# ThermalCamera.net
KiCad netlist of a schematic drawn in EAGLE
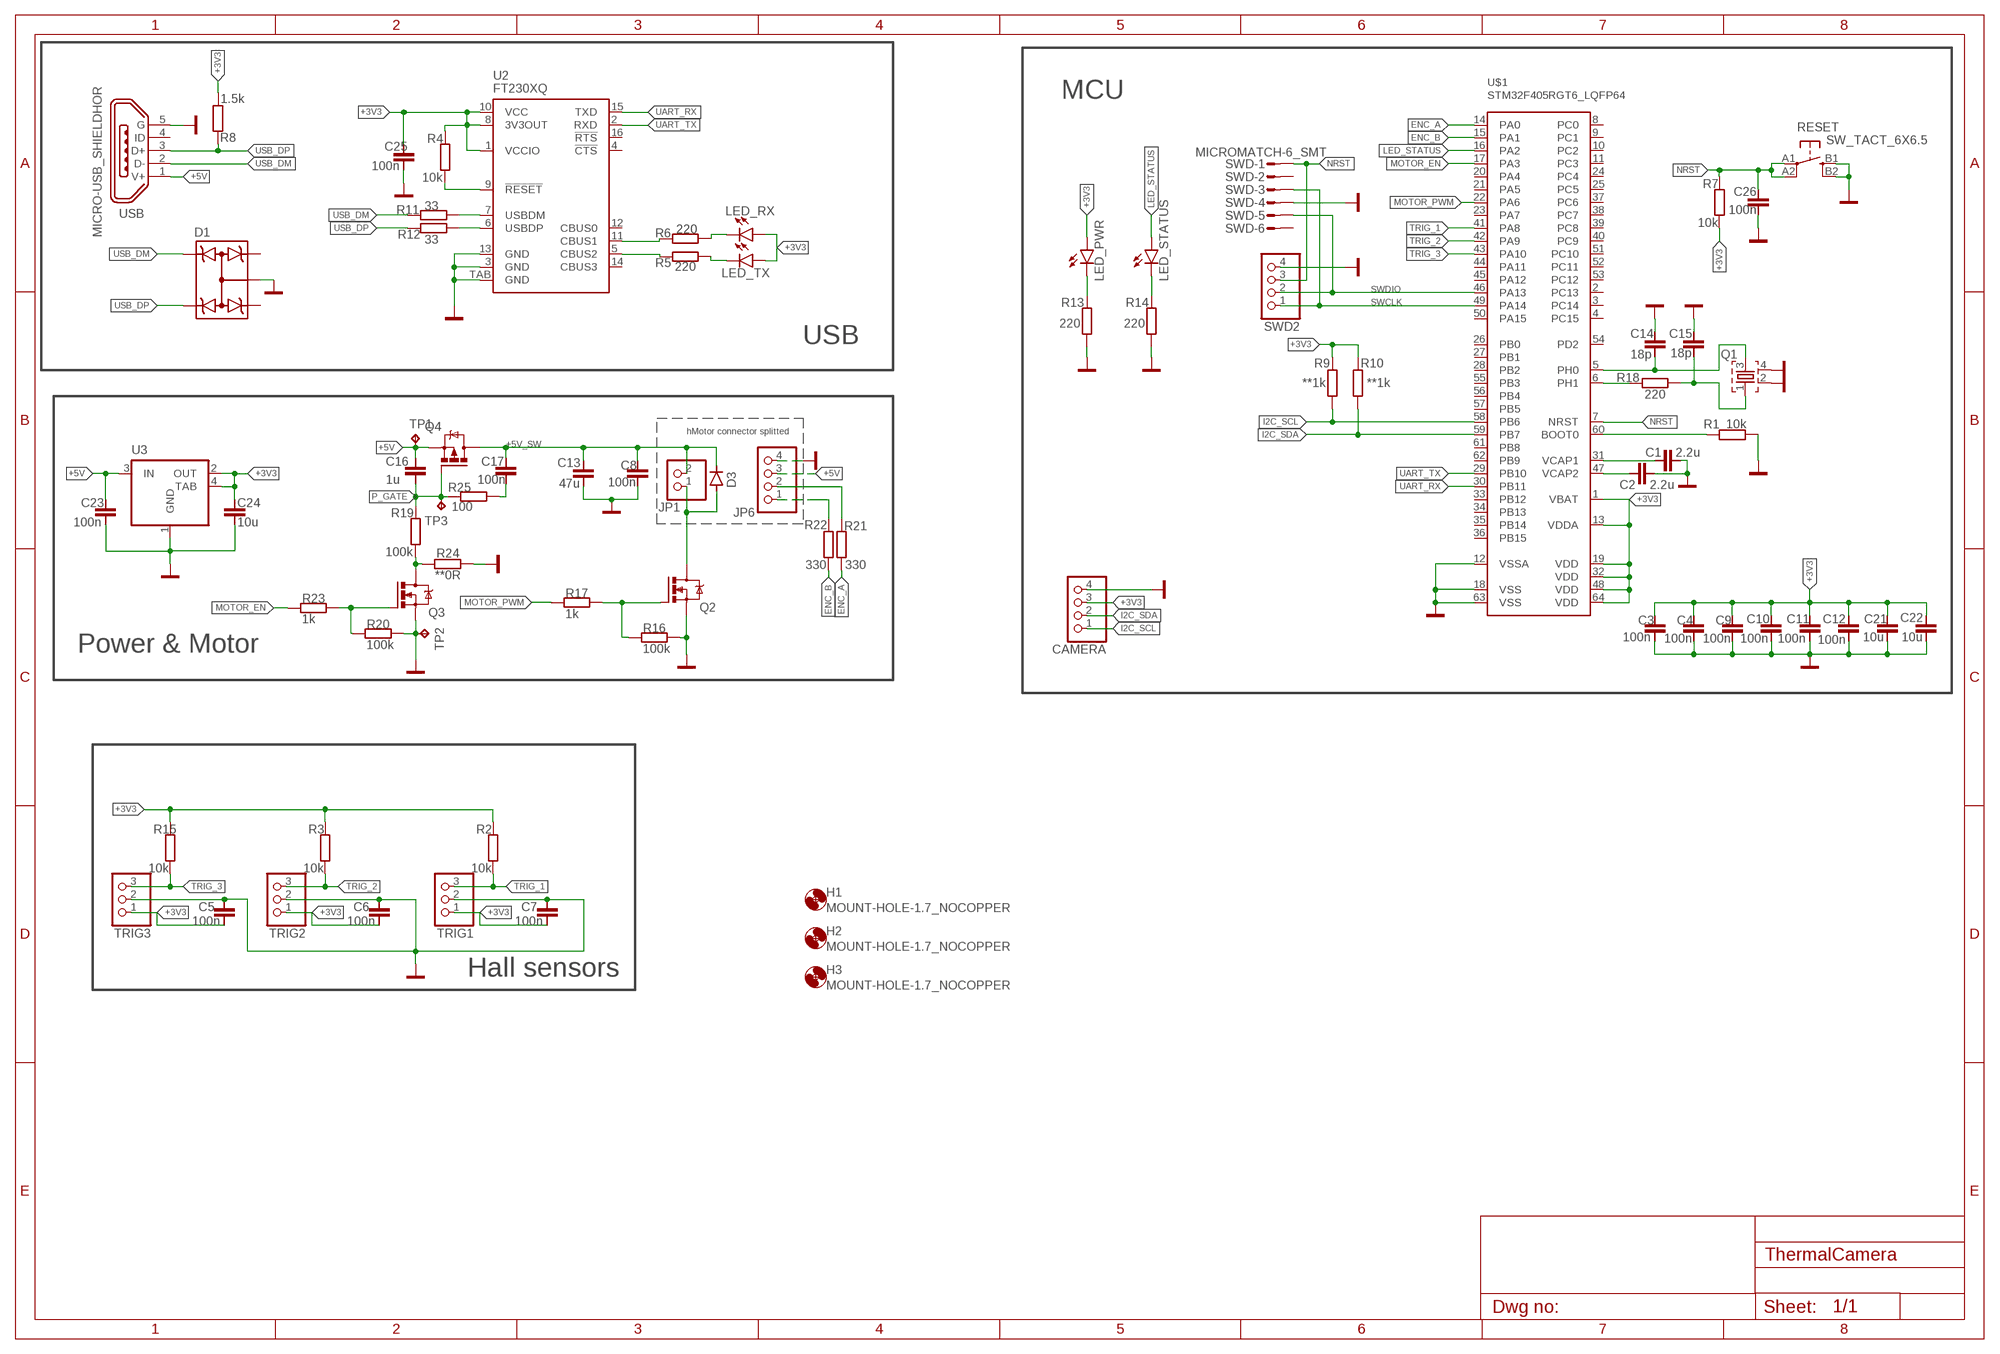
[diagram p0: schematic, sheet 1]

(export (version "E")
  (design (tool "Eeschema 10.0.6"))
  (components
    (comp (ref "C1")
      (value "2.2u")
      (footprint "eagle-import:0603")
      (libsource (lib "eagle-import") (part "CAP_H-0603"))
    )
    (comp (ref "C2")
      (value "2.2u")
      (footprint "eagle-import:0603")
      (libsource (lib "eagle-import") (part "CAP_H-0603"))
    )
    (comp (ref "C3")
      (value "100n")
      (footprint "eagle-import:0603")
      (libsource (lib "eagle-import") (part "CAP_H-0603"))
    )
    (comp (ref "C4")
      (value "100n")
      (footprint "eagle-import:0603")
      (libsource (lib "eagle-import") (part "CAP_H-0603"))
    )
    (comp (ref "C5")
      (value "100n")
      (footprint "eagle-import:0603")
      (libsource (lib "eagle-import") (part "CAP_H-0603"))
    )
    (comp (ref "C6")
      (value "100n")
      (footprint "eagle-import:0603")
      (libsource (lib "eagle-import") (part "CAP_H-0603"))
    )
    (comp (ref "C7")
      (value "100n")
      (footprint "eagle-import:0603")
      (libsource (lib "eagle-import") (part "CAP_H-0603"))
    )
    (comp (ref "C8")
      (value "100n")
      (footprint "eagle-import:0603")
      (libsource (lib "eagle-import") (part "CAP_H-0603"))
    )
    (comp (ref "C9")
      (value "100n")
      (footprint "eagle-import:0603")
      (libsource (lib "eagle-import") (part "CAP_H-0603"))
    )
    (comp (ref "C10")
      (value "100n")
      (footprint "eagle-import:0603")
      (libsource (lib "eagle-import") (part "CAP_H-0603"))
    )
    (comp (ref "C11")
      (value "100n")
      (footprint "eagle-import:0603")
      (libsource (lib "eagle-import") (part "CAP_H-0603"))
    )
    (comp (ref "C12")
      (value "100n")
      (footprint "eagle-import:0603")
      (libsource (lib "eagle-import") (part "CAP_H-0603"))
    )
    (comp (ref "C13")
      (value "47u")
      (footprint "eagle-import:0805")
      (libsource (lib "eagle-import") (part "CAP_H-0805"))
    )
    (comp (ref "C14")
      (value "18p")
      (footprint "eagle-import:0603")
      (libsource (lib "eagle-import") (part "CAP_H-0603"))
    )
    (comp (ref "C15")
      (value "18p")
      (footprint "eagle-import:0603")
      (libsource (lib "eagle-import") (part "CAP_H-0603"))
    )
    (comp (ref "C16")
      (value "1u")
      (footprint "eagle-import:0603")
      (libsource (lib "eagle-import") (part "CAP_H-0603"))
    )
    (comp (ref "C17")
      (value "100n")
      (footprint "eagle-import:0603")
      (libsource (lib "eagle-import") (part "CAP_H-0603"))
    )
    (comp (ref "C21")
      (value "10u")
      (footprint "eagle-import:0603")
      (libsource (lib "eagle-import") (part "CAP_H-0603"))
    )
    (comp (ref "C22")
      (value "10u")
      (footprint "eagle-import:0603")
      (libsource (lib "eagle-import") (part "CAP_H-0603"))
    )
    (comp (ref "C23")
      (value "100n")
      (footprint "eagle-import:0603")
      (libsource (lib "eagle-import") (part "CAP_H-0603"))
    )
    (comp (ref "C24")
      (value "10u")
      (footprint "eagle-import:0603")
      (libsource (lib "eagle-import") (part "CAP_H-0603"))
    )
    (comp (ref "C25")
      (value "100n")
      (footprint "eagle-import:0603")
      (libsource (lib "eagle-import") (part "CAP_H-0603"))
    )
    (comp (ref "C26")
      (value "100n")
      (footprint "eagle-import:0603")
      (libsource (lib "eagle-import") (part "CAP_H-0603"))
    )
    (comp (ref "CAMERA")
      (value "PINHD-1X4")
      (footprint "eagle-import:1X04")
      (fields (field (name "SPICEPREFIX") "E"))
      (libsource (lib "eagle-import") (part "PINHD-1X4"))
    )
    (comp (ref "D1")
      (value "TRANSIL-4")
      (footprint "eagle-import:SOT323-5")
      (libsource (lib "eagle-import") (part "TRANSIL-4"))
    )
    (comp (ref "D3")
      (value "BAR63-03")
      (footprint "eagle-import:SOD323")
      (libsource (lib "eagle-import") (part "BAR63-03"))
    )
    (comp (ref "H1")
      (value "MOUNT-HOLE-1.7_NOCOPPER")
      (footprint "eagle-import:1.7-NO_COPPER")
      (libsource (lib "eagle-import") (part "MOUNT-HOLE-1.7_NOCOPPER"))
    )
    (comp (ref "H2")
      (value "MOUNT-HOLE-1.7_NOCOPPER")
      (footprint "eagle-import:1.7-NO_COPPER")
      (libsource (lib "eagle-import") (part "MOUNT-HOLE-1.7_NOCOPPER"))
    )
    (comp (ref "H3")
      (value "MOUNT-HOLE-1.7_NOCOPPER")
      (footprint "eagle-import:1.7-NO_COPPER")
      (libsource (lib "eagle-import") (part "MOUNT-HOLE-1.7_NOCOPPER"))
    )
    (comp (ref "JP1")
      (value "PINHD-1X2")
      (footprint "eagle-import:1X02")
      (libsource (lib "eagle-import") (part "PINHD-1X2"))
    )
    (comp (ref "JP6")
      (value "PINHD-1X4")
      (footprint "eagle-import:1X04")
      (fields (field (name "SPICEPREFIX") "E"))
      (libsource (lib "eagle-import") (part "PINHD-1X4"))
    )
    (comp (ref "LED_PWR")
      (value "LEDCHIPLED_0603")
      (footprint "eagle-import:CHIPLED_0603")
      (libsource (lib "eagle-import") (part "LEDCHIPLED_0603"))
    )
    (comp (ref "LED_RX")
      (value "LEDCHIPLED_0603")
      (footprint "eagle-import:CHIPLED_0603")
      (libsource (lib "eagle-import") (part "LEDCHIPLED_0603"))
    )
    (comp (ref "LED_STATUS")
      (value "LEDCHIPLED_0603")
      (footprint "eagle-import:CHIPLED_0603")
      (libsource (lib "eagle-import") (part "LEDCHIPLED_0603"))
    )
    (comp (ref "LED_TX")
      (value "LEDCHIPLED_0603")
      (footprint "eagle-import:CHIPLED_0603")
      (libsource (lib "eagle-import") (part "LEDCHIPLED_0603"))
    )
    (comp (ref "Q1")
      (value "CRYSTAL_4PIN-5X3.2")
      (footprint "eagle-import:CRYSTAL_5X3.2_4PIN")
      (libsource (lib "eagle-import") (part "CRYSTAL_4PIN-5X3.2"))
    )
    (comp (ref "Q2")
      (value "NMOS-SOT23")
      (footprint "eagle-import:SOT23")
      (libsource (lib "eagle-import") (part "NMOS-SOT23"))
    )
    (comp (ref "Q3")
      (value "NMOS-SOT23")
      (footprint "eagle-import:SOT23")
      (libsource (lib "eagle-import") (part "NMOS-SOT23"))
    )
    (comp (ref "Q4")
      (value "PMOS-SOT23")
      (footprint "eagle-import:SOT23")
      (libsource (lib "eagle-import") (part "PMOS-SOT23"))
    )
    (comp (ref "R1")
      (value "10k")
      (footprint "eagle-import:0603")
      (libsource (lib "eagle-import") (part "RES_H-0603"))
    )
    (comp (ref "R2")
      (value "10k")
      (footprint "eagle-import:0603")
      (libsource (lib "eagle-import") (part "RES_H-0603"))
    )
    (comp (ref "R3")
      (value "10k")
      (footprint "eagle-import:0603")
      (libsource (lib "eagle-import") (part "RES_H-0603"))
    )
    (comp (ref "R4")
      (value "10k")
      (footprint "eagle-import:0603")
      (libsource (lib "eagle-import") (part "RES_H-0603"))
    )
    (comp (ref "R5")
      (value "220")
      (footprint "eagle-import:0603")
      (libsource (lib "eagle-import") (part "RES_H-0603"))
    )
    (comp (ref "R6")
      (value "220")
      (footprint "eagle-import:0603")
      (libsource (lib "eagle-import") (part "RES_H-0603"))
    )
    (comp (ref "R7")
      (value "10k")
      (footprint "eagle-import:0603")
      (libsource (lib "eagle-import") (part "RES_H-0603"))
    )
    (comp (ref "R8")
      (value "1.5k")
      (footprint "eagle-import:0603")
      (libsource (lib "eagle-import") (part "RES_H-0603"))
    )
    (comp (ref "R9")
      (value "**1k")
      (footprint "eagle-import:0603")
      (libsource (lib "eagle-import") (part "RES_H-0603"))
    )
    (comp (ref "R10")
      (value "**1k")
      (footprint "eagle-import:0603")
      (libsource (lib "eagle-import") (part "RES_H-0603"))
    )
    (comp (ref "R11")
      (value "33")
      (footprint "eagle-import:0603")
      (libsource (lib "eagle-import") (part "RES_H-0603"))
    )
    (comp (ref "R12")
      (value "33")
      (footprint "eagle-import:0603")
      (libsource (lib "eagle-import") (part "RES_H-0603"))
    )
    (comp (ref "R13")
      (value "220")
      (footprint "eagle-import:0603")
      (libsource (lib "eagle-import") (part "RES_H-0603"))
    )
    (comp (ref "R14")
      (value "220")
      (footprint "eagle-import:0603")
      (libsource (lib "eagle-import") (part "RES_H-0603"))
    )
    (comp (ref "R15")
      (value "10k")
      (footprint "eagle-import:0603")
      (libsource (lib "eagle-import") (part "RES_H-0603"))
    )
    (comp (ref "R16")
      (value "100k")
      (footprint "eagle-import:0603")
      (libsource (lib "eagle-import") (part "RES_H-0603"))
    )
    (comp (ref "R17")
      (value "1k")
      (footprint "eagle-import:0603")
      (libsource (lib "eagle-import") (part "RES_H-0603"))
    )
    (comp (ref "R18")
      (value "220")
      (footprint "eagle-import:0603")
      (libsource (lib "eagle-import") (part "RES_H-0603"))
    )
    (comp (ref "R19")
      (value "100k")
      (footprint "eagle-import:0603")
      (libsource (lib "eagle-import") (part "RES_H-0603"))
    )
    (comp (ref "R20")
      (value "100k")
      (footprint "eagle-import:0603")
      (libsource (lib "eagle-import") (part "RES_H-0603"))
    )
    (comp (ref "R21")
      (value "330")
      (footprint "eagle-import:0603")
      (libsource (lib "eagle-import") (part "RES_H-0603"))
    )
    (comp (ref "R22")
      (value "330")
      (footprint "eagle-import:0603")
      (libsource (lib "eagle-import") (part "RES_H-0603"))
    )
    (comp (ref "R23")
      (value "1k")
      (footprint "eagle-import:0603")
      (libsource (lib "eagle-import") (part "RES_H-0603"))
    )
    (comp (ref "R24")
      (value "**0R")
      (footprint "eagle-import:0603")
      (libsource (lib "eagle-import") (part "RES_H-0603"))
    )
    (comp (ref "R25")
      (value "100")
      (footprint "eagle-import:0603")
      (libsource (lib "eagle-import") (part "RES_H-0603"))
    )
    (comp (ref "RESET")
      (value "SW_TACT_6X6.5")
      (footprint "eagle-import:SW_TACT_6X6.5")
      (libsource (lib "eagle-import") (part "SW_TACT_6X6.5"))
    )
    (comp (ref "SWD")
      (value "MICROMATCH-6_SMT")
      (footprint "eagle-import:MICROMATCH-6_SMT")
      (libsource (lib "eagle-import") (part "MICROMATCH-6_SMT"))
    )
    (comp (ref "SWD2")
      (value "PINHD-1X4")
      (footprint "eagle-import:1X04")
      (libsource (lib "eagle-import") (part "PINHD-1X4"))
    )
    (comp (ref "TP1")
      (value "TPTP12R")
      (footprint "eagle-import:TP12R")
      (libsource (lib "eagle-import") (part "TPTP12R"))
    )
    (comp (ref "TP2")
      (value "TPTP12R")
      (footprint "eagle-import:TP12R")
      (libsource (lib "eagle-import") (part "TPTP12R"))
    )
    (comp (ref "TP3")
      (value "TPTP06R")
      (footprint "eagle-import:TP06R")
      (libsource (lib "eagle-import") (part "TPTP06R"))
    )
    (comp (ref "TRIG1")
      (value "PINHD-1X3")
      (footprint "eagle-import:1X03")
      (libsource (lib "eagle-import") (part "PINHD-1X3"))
    )
    (comp (ref "TRIG2")
      (value "PINHD-1X3")
      (footprint "eagle-import:1X03")
      (libsource (lib "eagle-import") (part "PINHD-1X3"))
    )
    (comp (ref "TRIG3")
      (value "PINHD-1X3")
      (footprint "eagle-import:1X03")
      (libsource (lib "eagle-import") (part "PINHD-1X3"))
    )
    (comp (ref "U$1")
      (value "STM32F405RGT6_LQFP64")
      (footprint "eagle-import:SQFP-S-10X10-64")
      (libsource (lib "eagle-import") (part "STM32F40XXX_LQFP64"))
    )
    (comp (ref "U2")
      (value "FT230XQ")
      (footprint "eagle-import:QFN16")
      (libsource (lib "eagle-import") (part "FT230XQ"))
    )
    (comp (ref "U3")
      (value "REG1117")
      (footprint "eagle-import:SOT223")
      (libsource (lib "eagle-import") (part "REG1117"))
    )
    (comp (ref "USB")
      (value "MICRO-USB_SHIELDHOR")
      (footprint "eagle-import:MICRO_USB_6_SHIELD")
      (libsource (lib "eagle-import") (part "MICRO-USB_SHIELDHOR"))
    )
  )
  (nets
    (net (code "1") (name "+3V3") (class "Default")
      (node (ref "C10") (pin "1") (pinfunction "1_1") (pintype "passive"))
      (node (ref "C11") (pin "1") (pinfunction "1_1") (pintype "passive"))
      (node (ref "C12") (pin "1") (pinfunction "1_1") (pintype "passive"))
      (node (ref "C21") (pin "1") (pinfunction "1_1") (pintype "passive"))
      (node (ref "C22") (pin "1") (pinfunction "1_1") (pintype "passive"))
      (node (ref "C24") (pin "1") (pinfunction "1_1") (pintype "passive"))
      (node (ref "C25") (pin "1") (pinfunction "1_1") (pintype "passive"))
      (node (ref "C3") (pin "1") (pinfunction "1_1") (pintype "passive"))
      (node (ref "C4") (pin "1") (pinfunction "1_1") (pintype "passive"))
      (node (ref "C5") (pin "2") (pinfunction "2_2") (pintype "passive"))
      (node (ref "C6") (pin "2") (pinfunction "2_2") (pintype "passive"))
      (node (ref "C7") (pin "2") (pinfunction "2_2") (pintype "passive"))
      (node (ref "C9") (pin "1") (pinfunction "1_1") (pintype "passive"))
      (node (ref "CAMERA") (pin "3") (pinfunction "3_3") (pintype "passive"))
      (node (ref "LED_PWR") (pin "A") (pinfunction "A_A") (pintype "passive"))
      (node (ref "LED_RX") (pin "A") (pinfunction "A_A") (pintype "passive"))
      (node (ref "LED_TX") (pin "A") (pinfunction "A_A") (pintype "passive"))
      (node (ref "R10") (pin "2") (pinfunction "2_2") (pintype "passive"))
      (node (ref "R15") (pin "2") (pinfunction "2_2") (pintype "passive"))
      (node (ref "R2") (pin "2") (pinfunction "2_2") (pintype "passive"))
      (node (ref "R3") (pin "2") (pinfunction "2_2") (pintype "passive"))
      (node (ref "R4") (pin "2") (pinfunction "2_2") (pintype "passive"))
      (node (ref "R7") (pin "1") (pinfunction "1_1") (pintype "passive"))
      (node (ref "R8") (pin "1") (pinfunction "1_1") (pintype "passive"))
      (node (ref "R9") (pin "2") (pinfunction "2_2") (pintype "passive"))
      (node (ref "TRIG1") (pin "1") (pinfunction "1_1") (pintype "passive"))
      (node (ref "TRIG2") (pin "1") (pinfunction "1_1") (pintype "passive"))
      (node (ref "TRIG3") (pin "1") (pinfunction "1_1") (pintype "passive"))
      (node (ref "U$1") (pin "1") (pinfunction "VBAT_1") (pintype "bidirectional"))
      (node (ref "U$1") (pin "13") (pinfunction "VDDA_13") (pintype "bidirectional"))
      (node (ref "U$1") (pin "19") (pinfunction "VDD_19") (pintype "bidirectional"))
      (node (ref "U$1") (pin "32") (pinfunction "VDD_32") (pintype "bidirectional"))
      (node (ref "U$1") (pin "48") (pinfunction "VDD_48") (pintype "bidirectional"))
      (node (ref "U$1") (pin "64") (pinfunction "VDD_64") (pintype "bidirectional"))
      (node (ref "U2") (pin "1") (pinfunction "VCCIO_1") (pintype "power_in"))
      (node (ref "U2") (pin "10") (pinfunction "VCC_10") (pintype "power_in"))
      (node (ref "U2") (pin "8") (pinfunction "3V3OUT_8") (pintype "output"))
      (node (ref "U3") (pin "2") (pinfunction "OUT_2") (pintype "output"))
      (node (ref "U3") (pin "4") (pinfunction "TAB_4") (pintype "output"))
    )
    (net (code "2") (name "+5V") (class "Default")
      (node (ref "C16") (pin "1") (pinfunction "1_1") (pintype "passive"))
      (node (ref "C23") (pin "1") (pinfunction "1_1") (pintype "passive"))
      (node (ref "JP6") (pin "3") (pinfunction "3_3") (pintype "passive"))
      (node (ref "Q4") (pin "2") (pinfunction "S_2") (pintype "passive"))
      (node (ref "TP1") (pin "TP") (pinfunction "TP_TP") (pintype "input"))
      (node (ref "U3") (pin "3") (pinfunction "IN_3") (pintype "input"))
      (node (ref "USB") (pin "1") (pinfunction "V+_1") (pintype "passive"))
    )
    (net (code "3") (name "/+5V_SW") (class "Default")
      (node (ref "C13") (pin "1") (pinfunction "1_1") (pintype "passive"))
      (node (ref "C17") (pin "1") (pinfunction "1_1") (pintype "passive"))
      (node (ref "C8") (pin "1") (pinfunction "1_1") (pintype "passive"))
      (node (ref "D3") (pin "1") (pinfunction "C_1") (pintype "passive"))
      (node (ref "JP1") (pin "2") (pinfunction "2_2") (pintype "passive"))
      (node (ref "Q4") (pin "3") (pinfunction "D_3") (pintype "passive"))
    )
    (net (code "4") (name "/SWCLK") (class "Default")
      (node (ref "SWD") (pin "P$3") (pinfunction "S_P$3") (pintype "passive"))
      (node (ref "SWD2") (pin "1") (pinfunction "1_1") (pintype "passive"))
      (node (ref "U$1") (pin "49") (pinfunction "PA14_49") (pintype "bidirectional"))
    )
    (net (code "5") (name "/SWDIO") (class "Default")
      (node (ref "SWD") (pin "P$5") (pinfunction "S_P$5") (pintype "passive"))
      (node (ref "SWD2") (pin "2") (pinfunction "2_2") (pintype "passive"))
      (node (ref "U$1") (pin "46") (pinfunction "PA13_46") (pintype "bidirectional"))
    )
    (net (code "6") (name "ENC_A") (class "Default")
      (node (ref "R21") (pin "2") (pinfunction "2_2") (pintype "passive"))
      (node (ref "U$1") (pin "14") (pinfunction "PA0_14") (pintype "bidirectional"))
    )
    (net (code "7") (name "ENC_B") (class "Default")
      (node (ref "R22") (pin "1") (pinfunction "1_1") (pintype "passive"))
      (node (ref "U$1") (pin "15") (pinfunction "PA1_15") (pintype "bidirectional"))
    )
    (net (code "8") (name "GND") (class "Default")
      (node (ref "C1") (pin "2") (pinfunction "2_2") (pintype "passive"))
      (node (ref "C10") (pin "2") (pinfunction "2_2") (pintype "passive"))
      (node (ref "C11") (pin "2") (pinfunction "2_2") (pintype "passive"))
      (node (ref "C12") (pin "2") (pinfunction "2_2") (pintype "passive"))
      (node (ref "C13") (pin "2") (pinfunction "2_2") (pintype "passive"))
      (node (ref "C14") (pin "1") (pinfunction "1_1") (pintype "passive"))
      (node (ref "C15") (pin "1") (pinfunction "1_1") (pintype "passive"))
      (node (ref "C2") (pin "2") (pinfunction "2_2") (pintype "passive"))
      (node (ref "C21") (pin "2") (pinfunction "2_2") (pintype "passive"))
      (node (ref "C22") (pin "2") (pinfunction "2_2") (pintype "passive"))
      (node (ref "C23") (pin "2") (pinfunction "2_2") (pintype "passive"))
      (node (ref "C24") (pin "2") (pinfunction "2_2") (pintype "passive"))
      (node (ref "C25") (pin "2") (pinfunction "2_2") (pintype "passive"))
      (node (ref "C26") (pin "2") (pinfunction "2_2") (pintype "passive"))
      (node (ref "C3") (pin "2") (pinfunction "2_2") (pintype "passive"))
      (node (ref "C4") (pin "2") (pinfunction "2_2") (pintype "passive"))
      (node (ref "C5") (pin "1") (pinfunction "1_1") (pintype "passive"))
      (node (ref "C6") (pin "1") (pinfunction "1_1") (pintype "passive"))
      (node (ref "C7") (pin "1") (pinfunction "1_1") (pintype "passive"))
      (node (ref "C8") (pin "2") (pinfunction "2_2") (pintype "passive"))
      (node (ref "C9") (pin "2") (pinfunction "2_2") (pintype "passive"))
      (node (ref "CAMERA") (pin "4") (pinfunction "4_4") (pintype "passive"))
      (node (ref "D1") (pin "2") (pinfunction "2_2") (pintype "passive"))
      (node (ref "JP6") (pin "4") (pinfunction "4_4") (pintype "passive"))
      (node (ref "Q1") (pin "2") (pinfunction "2_2") (pintype "passive"))
      (node (ref "Q1") (pin "4") (pinfunction "4_4") (pintype "passive"))
      (node (ref "Q2") (pin "2") (pinfunction "S_2") (pintype "passive"))
      (node (ref "Q3") (pin "2") (pinfunction "S_2") (pintype "passive"))
      (node (ref "R1") (pin "2") (pinfunction "2_2") (pintype "passive"))
      (node (ref "R13") (pin "2") (pinfunction "2_2") (pintype "passive"))
      (node (ref "R14") (pin "2") (pinfunction "2_2") (pintype "passive"))
      (node (ref "R16") (pin "1") (pinfunction "1_1") (pintype "passive"))
      (node (ref "R20") (pin "1") (pinfunction "1_1") (pintype "passive"))
      (node (ref "R24") (pin "1") (pinfunction "1_1") (pintype "passive"))
      (node (ref "RESET") (pin "B1") (pinfunction "S_B1") (pintype "passive"))
      (node (ref "RESET") (pin "B2") (pinfunction "S1_B2") (pintype "passive"))
      (node (ref "SWD") (pin "P$4") (pinfunction "S_P$4") (pintype "passive"))
      (node (ref "SWD2") (pin "4") (pinfunction "4_4") (pintype "passive"))
      (node (ref "TP2") (pin "TP") (pinfunction "TP_TP") (pintype "input"))
      (node (ref "TRIG1") (pin "2") (pinfunction "2_2") (pintype "passive"))
      (node (ref "TRIG2") (pin "2") (pinfunction "2_2") (pintype "passive"))
      (node (ref "TRIG3") (pin "2") (pinfunction "2_2") (pintype "passive"))
      (node (ref "U$1") (pin "12") (pinfunction "VSSA_12") (pintype "bidirectional"))
      (node (ref "U$1") (pin "18") (pinfunction "VSS_18") (pintype "bidirectional"))
      (node (ref "U$1") (pin "63") (pinfunction "VSS_63") (pintype "bidirectional"))
      (node (ref "U2") (pin "13") (pinfunction "GND_13") (pintype "power_in"))
      (node (ref "U2") (pin "3") (pinfunction "GND_3") (pintype "power_in"))
      (node (ref "U2") (pin "TAB") (pinfunction "GND_TAB") (pintype "power_in"))
      (node (ref "U3") (pin "1") (pinfunction "GND_1") (pintype "power_in"))
      (node (ref "USB") (pin "5") (pinfunction "G_5") (pintype "passive"))
    )
    (net (code "9") (name "I2C_SCL") (class "Default")
      (node (ref "CAMERA") (pin "1") (pinfunction "1_1") (pintype "passive"))
      (node (ref "R9") (pin "1") (pinfunction "1_1") (pintype "passive"))
      (node (ref "U$1") (pin "58") (pinfunction "PB6_58") (pintype "bidirectional"))
    )
    (net (code "10") (name "I2C_SDA") (class "Default")
      (node (ref "CAMERA") (pin "2") (pinfunction "2_2") (pintype "passive"))
      (node (ref "R10") (pin "1") (pinfunction "1_1") (pintype "passive"))
      (node (ref "U$1") (pin "59") (pinfunction "PB7_59") (pintype "bidirectional"))
    )
    (net (code "11") (name "LED_STATUS") (class "Default")
      (node (ref "LED_STATUS") (pin "A") (pinfunction "A_A") (pintype "passive"))
      (node (ref "U$1") (pin "16") (pinfunction "PA2_16") (pintype "bidirectional"))
    )
    (net (code "12") (name "MOTOR_EN") (class "Default")
      (node (ref "R23") (pin "2") (pinfunction "2_2") (pintype "passive"))
      (node (ref "U$1") (pin "17") (pinfunction "PA3_17") (pintype "bidirectional"))
    )
    (net (code "13") (name "MOTOR_PWM") (class "Default")
      (node (ref "R17") (pin "2") (pinfunction "2_2") (pintype "passive"))
      (node (ref "U$1") (pin "22") (pinfunction "PA6_22") (pintype "bidirectional"))
    )
    (net (code "14") (name "NRST") (class "Default")
      (node (ref "C26") (pin "1") (pinfunction "1_1") (pintype "passive"))
      (node (ref "R7") (pin "2") (pinfunction "2_2") (pintype "passive"))
      (node (ref "RESET") (pin "A1") (pinfunction "P_A1") (pintype "passive"))
      (node (ref "RESET") (pin "A2") (pinfunction "P1_A2") (pintype "passive"))
      (node (ref "SWD") (pin "P$1") (pinfunction "S_P$1") (pintype "passive"))
      (node (ref "SWD2") (pin "3") (pinfunction "3_3") (pintype "passive"))
      (node (ref "U$1") (pin "7") (pinfunction "NRST_7") (pintype "bidirectional"))
    )
    (net (code "15") (name "Net-(C15-Pad2)") (class "Default")
      (node (ref "C15") (pin "2") (pinfunction "2_2") (pintype "passive"))
      (node (ref "Q1") (pin "1") (pinfunction "1_1") (pintype "passive"))
      (node (ref "R18") (pin "2") (pinfunction "2_2") (pintype "passive"))
    )
    (net (code "16") (name "Net-(C17-Pad2)") (class "Default")
      (node (ref "C17") (pin "2") (pinfunction "2_2") (pintype "passive"))
      (node (ref "R25") (pin "1") (pinfunction "1_1") (pintype "passive"))
    )
    (net (code "17") (name "Net-(D3-A)") (class "Default")
      (node (ref "D3") (pin "2") (pinfunction "A_2") (pintype "passive"))
      (node (ref "JP1") (pin "1") (pinfunction "1_1") (pintype "passive"))
      (node (ref "Q2") (pin "3") (pinfunction "D_3") (pintype "passive"))
    )
    (net (code "18") (name "Net-(JP6-Pad1)") (class "Default")
      (node (ref "JP6") (pin "1") (pinfunction "1_1") (pintype "passive"))
      (node (ref "R22") (pin "2") (pinfunction "2_2") (pintype "passive"))
    )
    (net (code "19") (name "Net-(JP6-Pad2)") (class "Default")
      (node (ref "JP6") (pin "2") (pinfunction "2_2") (pintype "passive"))
      (node (ref "R21") (pin "1") (pinfunction "1_1") (pintype "passive"))
    )
    (net (code "20") (name "Net-(LED_PWR-PadC)") (class "Default")
      (node (ref "LED_PWR") (pin "C") (pinfunction "C_C") (pintype "passive"))
      (node (ref "R13") (pin "1") (pinfunction "1_1") (pintype "passive"))
    )
    (net (code "21") (name "Net-(LED_RX-PadC)") (class "Default")
      (node (ref "LED_RX") (pin "C") (pinfunction "C_C") (pintype "passive"))
      (node (ref "R6") (pin "1") (pinfunction "1_1") (pintype "passive"))
    )
    (net (code "22") (name "Net-(LED_STATUS-PadC)") (class "Default")
      (node (ref "LED_STATUS") (pin "C") (pinfunction "C_C") (pintype "passive"))
      (node (ref "R14") (pin "1") (pinfunction "1_1") (pintype "passive"))
    )
    (net (code "23") (name "Net-(LED_TX-PadC)") (class "Default")
      (node (ref "LED_TX") (pin "C") (pinfunction "C_C") (pintype "passive"))
      (node (ref "R5") (pin "1") (pinfunction "1_1") (pintype "passive"))
    )
    (net (code "24") (name "Net-(Q2-G)") (class "Default")
      (node (ref "Q2") (pin "1") (pinfunction "G_1") (pintype "passive"))
      (node (ref "R16") (pin "2") (pinfunction "2_2") (pintype "passive"))
      (node (ref "R17") (pin "1") (pinfunction "1_1") (pintype "passive"))
    )
    (net (code "25") (name "Net-(Q3-D)") (class "Default")
      (node (ref "Q3") (pin "3") (pinfunction "D_3") (pintype "passive"))
      (node (ref "R19") (pin "1") (pinfunction "1_1") (pintype "passive"))
      (node (ref "R24") (pin "2") (pinfunction "2_2") (pintype "passive"))
    )
    (net (code "26") (name "Net-(Q3-G)") (class "Default")
      (node (ref "Q3") (pin "1") (pinfunction "G_1") (pintype "passive"))
      (node (ref "R20") (pin "2") (pinfunction "2_2") (pintype "passive"))
      (node (ref "R23") (pin "1") (pinfunction "1_1") (pintype "passive"))
    )
    (net (code "27") (name "Net-(U$1-BOOT0)") (class "Default")
      (node (ref "R1") (pin "1") (pinfunction "1_1") (pintype "passive"))
      (node (ref "U$1") (pin "60") (pinfunction "BOOT0_60") (pintype "bidirectional"))
    )
    (net (code "28") (name "Net-(U$1-PH0)") (class "Default")
      (node (ref "C14") (pin "2") (pinfunction "2_2") (pintype "passive"))
      (node (ref "Q1") (pin "3") (pinfunction "3_3") (pintype "passive"))
      (node (ref "U$1") (pin "5") (pinfunction "PH0_5") (pintype "bidirectional"))
    )
    (net (code "29") (name "Net-(U$1-PH1)") (class "Default")
      (node (ref "R18") (pin "1") (pinfunction "1_1") (pintype "passive"))
      (node (ref "U$1") (pin "6") (pinfunction "PH1_6") (pintype "bidirectional"))
    )
    (net (code "30") (name "Net-(U$1-VCAP1)") (class "Default")
      (node (ref "C1") (pin "1") (pinfunction "1_1") (pintype "passive"))
      (node (ref "U$1") (pin "31") (pinfunction "VCAP1_31") (pintype "bidirectional"))
    )
    (net (code "31") (name "Net-(U$1-VCAP2)") (class "Default")
      (node (ref "C2") (pin "1") (pinfunction "1_1") (pintype "passive"))
      (node (ref "U$1") (pin "47") (pinfunction "VCAP2_47") (pintype "bidirectional"))
    )
    (net (code "32") (name "Net-(U2-CBUS1)") (class "Default")
      (node (ref "R6") (pin "2") (pinfunction "2_2") (pintype "passive"))
      (node (ref "U2") (pin "11") (pinfunction "CBUS1_11") (pintype "bidirectional"))
    )
    (net (code "33") (name "Net-(U2-CBUS2)") (class "Default")
      (node (ref "R5") (pin "2") (pinfunction "2_2") (pintype "passive"))
      (node (ref "U2") (pin "5") (pinfunction "CBUS2_5") (pintype "bidirectional"))
    )
    (net (code "34") (name "Net-(U2-USBDM)") (class "Default")
      (node (ref "R11") (pin "1") (pinfunction "1_1") (pintype "passive"))
      (node (ref "U2") (pin "7") (pinfunction "USBDM_7") (pintype "input"))
    )
    (net (code "35") (name "Net-(U2-USBDP)") (class "Default")
      (node (ref "R12") (pin "1") (pinfunction "1_1") (pintype "passive"))
      (node (ref "U2") (pin "6") (pinfunction "USBDP_6") (pintype "input"))
    )
    (net (code "36") (name "Net-(U2-~{RESET})") (class "Default")
      (node (ref "R4") (pin "1") (pinfunction "1_1") (pintype "passive"))
      (node (ref "U2") (pin "9") (pinfunction "~{RESET}_9") (pintype "input"))
    )
    (net (code "37") (name "P_GATE") (class "Default")
      (node (ref "C16") (pin "2") (pinfunction "2_2") (pintype "passive"))
      (node (ref "Q4") (pin "1") (pinfunction "G_1") (pintype "passive"))
      (node (ref "R19") (pin "2") (pinfunction "2_2") (pintype "passive"))
      (node (ref "R25") (pin "2") (pinfunction "2_2") (pintype "passive"))
      (node (ref "TP3") (pin "TP") (pinfunction "TP_TP") (pintype "input"))
    )
    (net (code "38") (name "TRIG_1") (class "Default")
      (node (ref "R2") (pin "1") (pinfunction "1_1") (pintype "passive"))
      (node (ref "TRIG1") (pin "3") (pinfunction "3_3") (pintype "passive"))
      (node (ref "U$1") (pin "41") (pinfunction "PA8_41") (pintype "bidirectional"))
    )
    (net (code "39") (name "TRIG_2") (class "Default")
      (node (ref "R3") (pin "1") (pinfunction "1_1") (pintype "passive"))
      (node (ref "TRIG2") (pin "3") (pinfunction "3_3") (pintype "passive"))
      (node (ref "U$1") (pin "42") (pinfunction "PA9_42") (pintype "bidirectional"))
    )
    (net (code "40") (name "TRIG_3") (class "Default")
      (node (ref "R15") (pin "1") (pinfunction "1_1") (pintype "passive"))
      (node (ref "TRIG3") (pin "3") (pinfunction "3_3") (pintype "passive"))
      (node (ref "U$1") (pin "43") (pinfunction "PA10_43") (pintype "bidirectional"))
    )
    (net (code "41") (name "UART_RX") (class "Default")
      (node (ref "U$1") (pin "30") (pinfunction "PB11_30") (pintype "bidirectional"))
      (node (ref "U2") (pin "15") (pinfunction "TXD_15") (pintype "output"))
    )
    (net (code "42") (name "UART_TX") (class "Default")
      (node (ref "U$1") (pin "29") (pinfunction "PB10_29") (pintype "bidirectional"))
      (node (ref "U2") (pin "2") (pinfunction "RXD_2") (pintype "input"))
    )
    (net (code "43") (name "USB_DM") (class "Default")
      (node (ref "D1") (pin "4") (pinfunction "4_4") (pintype "passive"))
      (node (ref "R11") (pin "2") (pinfunction "2_2") (pintype "passive"))
      (node (ref "USB") (pin "2") (pinfunction "D-_2") (pintype "passive"))
    )
    (net (code "44") (name "USB_DP") (class "Default")
      (node (ref "D1") (pin "5") (pinfunction "5_5") (pintype "passive"))
      (node (ref "R12") (pin "2") (pinfunction "2_2") (pintype "passive"))
      (node (ref "R8") (pin "2") (pinfunction "2_2") (pintype "passive"))
      (node (ref "USB") (pin "3") (pinfunction "D+_3") (pintype "passive"))
    )
    (net (code "45") (name "unconnected-(D1-Pad1)") (class "Default")
      (node (ref "D1") (pin "1") (pinfunction "1_1") (pintype "passive"))
    )
    (net (code "46") (name "unconnected-(D1-Pad3)") (class "Default")
      (node (ref "D1") (pin "3") (pinfunction "3_3") (pintype "passive"))
    )
    (net (code "47") (name "unconnected-(SWDB-S-PadP$2)") (class "Default")
      (node (ref "SWD") (pin "P$2") (pinfunction "S_P$2") (pintype "passive"))
    )
    (net (code "48") (name "unconnected-(SWDF-S-PadP$6)") (class "Default")
      (node (ref "SWD") (pin "P$6") (pinfunction "S_P$6") (pintype "passive"))
    )
    (net (code "49") (name "unconnected-(U$1-PA4-Pad20)") (class "Default")
      (node (ref "U$1") (pin "20") (pinfunction "PA4_20") (pintype "bidirectional"))
    )
    (net (code "50") (name "unconnected-(U$1-PA5-Pad21)") (class "Default")
      (node (ref "U$1") (pin "21") (pinfunction "PA5_21") (pintype "bidirectional"))
    )
    (net (code "51") (name "unconnected-(U$1-PA7-Pad23)") (class "Default")
      (node (ref "U$1") (pin "23") (pinfunction "PA7_23") (pintype "bidirectional"))
    )
    (net (code "52") (name "unconnected-(U$1-PA11-Pad44)") (class "Default")
      (node (ref "U$1") (pin "44") (pinfunction "PA11_44") (pintype "bidirectional"))
    )
    (net (code "53") (name "unconnected-(U$1-PA12-Pad45)") (class "Default")
      (node (ref "U$1") (pin "45") (pinfunction "PA12_45") (pintype "bidirectional"))
    )
    (net (code "54") (name "unconnected-(U$1-PA15-Pad50)") (class "Default")
      (node (ref "U$1") (pin "50") (pinfunction "PA15_50") (pintype "bidirectional"))
    )
    (net (code "55") (name "unconnected-(U$1-PB0-Pad26)") (class "Default")
      (node (ref "U$1") (pin "26") (pinfunction "PB0_26") (pintype "bidirectional"))
    )
    (net (code "56") (name "unconnected-(U$1-PB1-Pad27)") (class "Default")
      (node (ref "U$1") (pin "27") (pinfunction "PB1_27") (pintype "bidirectional"))
    )
    (net (code "57") (name "unconnected-(U$1-PB2-Pad28)") (class "Default")
      (node (ref "U$1") (pin "28") (pinfunction "PB2_28") (pintype "bidirectional"))
    )
    (net (code "58") (name "unconnected-(U$1-PB3-Pad55)") (class "Default")
      (node (ref "U$1") (pin "55") (pinfunction "PB3_55") (pintype "bidirectional"))
    )
    (net (code "59") (name "unconnected-(U$1-PB4-Pad56)") (class "Default")
      (node (ref "U$1") (pin "56") (pinfunction "PB4_56") (pintype "bidirectional"))
    )
    (net (code "60") (name "unconnected-(U$1-PB5-Pad57)") (class "Default")
      (node (ref "U$1") (pin "57") (pinfunction "PB5_57") (pintype "bidirectional"))
    )
    (net (code "61") (name "unconnected-(U$1-PB8-Pad61)") (class "Default")
      (node (ref "U$1") (pin "61") (pinfunction "PB8_61") (pintype "bidirectional"))
    )
    (net (code "62") (name "unconnected-(U$1-PB9-Pad62)") (class "Default")
      (node (ref "U$1") (pin "62") (pinfunction "PB9_62") (pintype "bidirectional"))
    )
    (net (code "63") (name "unconnected-(U$1-PB12-Pad33)") (class "Default")
      (node (ref "U$1") (pin "33") (pinfunction "PB12_33") (pintype "bidirectional"))
    )
    (net (code "64") (name "unconnected-(U$1-PB13-Pad34)") (class "Default")
      (node (ref "U$1") (pin "34") (pinfunction "PB13_34") (pintype "bidirectional"))
    )
    (net (code "65") (name "unconnected-(U$1-PB14-Pad35)") (class "Default")
      (node (ref "U$1") (pin "35") (pinfunction "PB14_35") (pintype "bidirectional"))
    )
    (net (code "66") (name "unconnected-(U$1-PB15-Pad36)") (class "Default")
      (node (ref "U$1") (pin "36") (pinfunction "PB15_36") (pintype "bidirectional"))
    )
    (net (code "67") (name "unconnected-(U$1-PC0-Pad8)") (class "Default")
      (node (ref "U$1") (pin "8") (pinfunction "PC0_8") (pintype "bidirectional"))
    )
    (net (code "68") (name "unconnected-(U$1-PC1-Pad9)") (class "Default")
      (node (ref "U$1") (pin "9") (pinfunction "PC1_9") (pintype "bidirectional"))
    )
    (net (code "69") (name "unconnected-(U$1-PC2-Pad10)") (class "Default")
      (node (ref "U$1") (pin "10") (pinfunction "PC2_10") (pintype "bidirectional"))
    )
    (net (code "70") (name "unconnected-(U$1-PC3-Pad11)") (class "Default")
      (node (ref "U$1") (pin "11") (pinfunction "PC3_11") (pintype "bidirectional"))
    )
    (net (code "71") (name "unconnected-(U$1-PC4-Pad24)") (class "Default")
      (node (ref "U$1") (pin "24") (pinfunction "PC4_24") (pintype "bidirectional"))
    )
    (net (code "72") (name "unconnected-(U$1-PC5-Pad25)") (class "Default")
      (node (ref "U$1") (pin "25") (pinfunction "PC5_25") (pintype "bidirectional"))
    )
    (net (code "73") (name "unconnected-(U$1-PC6-Pad37)") (class "Default")
      (node (ref "U$1") (pin "37") (pinfunction "PC6_37") (pintype "bidirectional"))
    )
    (net (code "74") (name "unconnected-(U$1-PC7-Pad38)") (class "Default")
      (node (ref "U$1") (pin "38") (pinfunction "PC7_38") (pintype "bidirectional"))
    )
    (net (code "75") (name "unconnected-(U$1-PC8-Pad39)") (class "Default")
      (node (ref "U$1") (pin "39") (pinfunction "PC8_39") (pintype "bidirectional"))
    )
    (net (code "76") (name "unconnected-(U$1-PC9-Pad40)") (class "Default")
      (node (ref "U$1") (pin "40") (pinfunction "PC9_40") (pintype "bidirectional"))
    )
    (net (code "77") (name "unconnected-(U$1-PC10-Pad51)") (class "Default")
      (node (ref "U$1") (pin "51") (pinfunction "PC10_51") (pintype "bidirectional"))
    )
    (net (code "78") (name "unconnected-(U$1-PC11-Pad52)") (class "Default")
      (node (ref "U$1") (pin "52") (pinfunction "PC11_52") (pintype "bidirectional"))
    )
    (net (code "79") (name "unconnected-(U$1-PC12-Pad53)") (class "Default")
      (node (ref "U$1") (pin "53") (pinfunction "PC12_53") (pintype "bidirectional"))
    )
    (net (code "80") (name "unconnected-(U$1-PC13-Pad2)") (class "Default")
      (node (ref "U$1") (pin "2") (pinfunction "PC13_2") (pintype "bidirectional"))
    )
    (net (code "81") (name "unconnected-(U$1-PC14-Pad3)") (class "Default")
      (node (ref "U$1") (pin "3") (pinfunction "PC14_3") (pintype "bidirectional"))
    )
    (net (code "82") (name "unconnected-(U$1-PC15-Pad4)") (class "Default")
      (node (ref "U$1") (pin "4") (pinfunction "PC15_4") (pintype "bidirectional"))
    )
    (net (code "83") (name "unconnected-(U$1-PD2-Pad54)") (class "Default")
      (node (ref "U$1") (pin "54") (pinfunction "PD2_54") (pintype "bidirectional"))
    )
    (net (code "84") (name "unconnected-(U2-CBUS0-Pad12)") (class "Default")
      (node (ref "U2") (pin "12") (pinfunction "CBUS0_12") (pintype "bidirectional"))
    )
    (net (code "85") (name "unconnected-(U2-CBUS3-Pad14)") (class "Default")
      (node (ref "U2") (pin "14") (pinfunction "CBUS3_14") (pintype "bidirectional"))
    )
    (net (code "86") (name "unconnected-(U2-~{CTS}-Pad4)") (class "Default")
      (node (ref "U2") (pin "4") (pinfunction "~{CTS}_4") (pintype "input"))
    )
    (net (code "87") (name "unconnected-(U2-~{RTS}-Pad16)") (class "Default")
      (node (ref "U2") (pin "16") (pinfunction "~{RTS}_16") (pintype "output"))
    )
    (net (code "88") (name "unconnected-(USBA-ID-Pad4)") (class "Default")
      (node (ref "USB") (pin "4") (pinfunction "ID_4") (pintype "passive"))
    )
  )
)
